# discrim.net
KiCad netlist of a schematic drawn in EAGLE
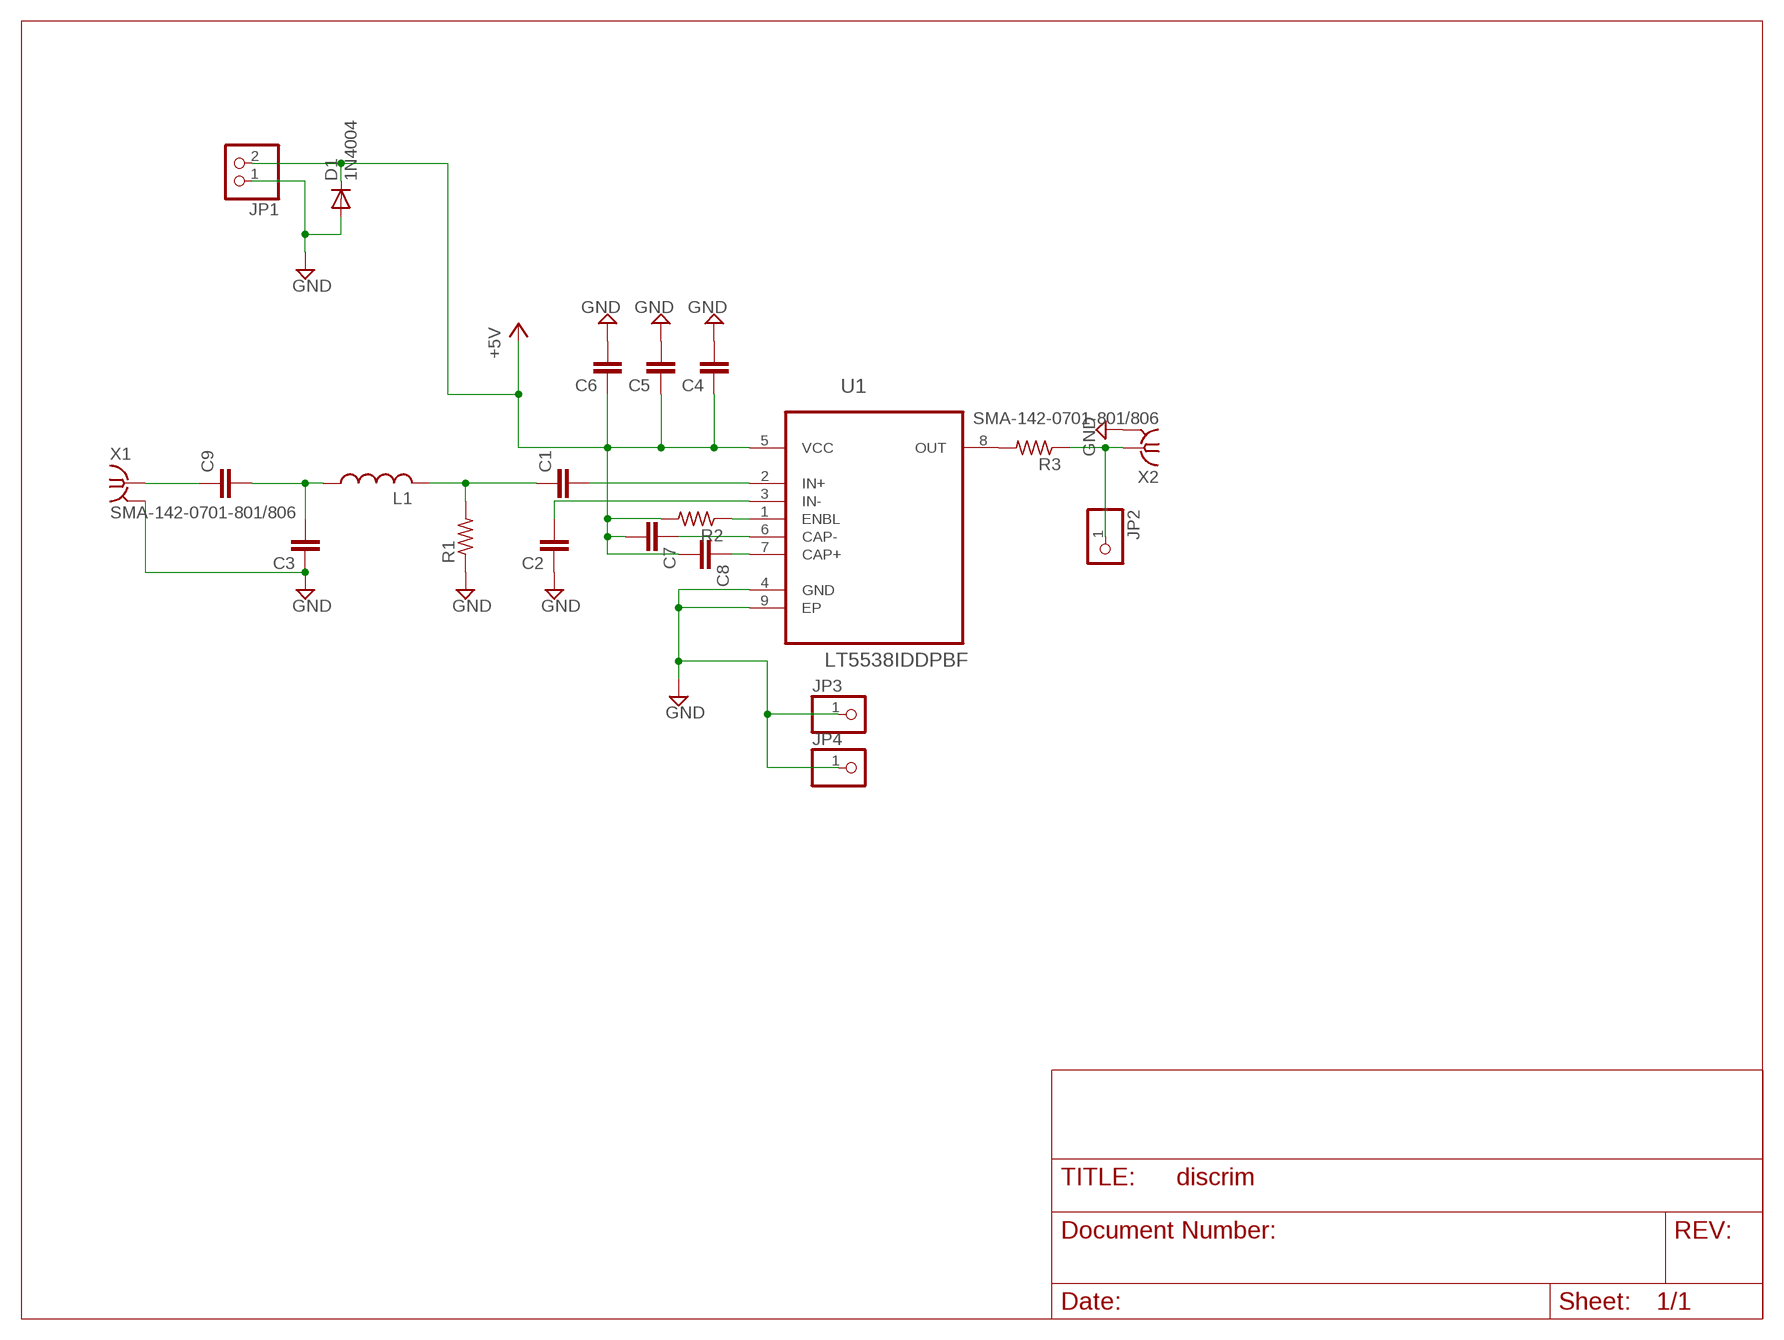
[diagram p0: schematic, sheet 1]

(export (version "E")
  (design (tool "Eeschema 10.0.6"))
  (components
    (comp (ref "C1")
      (value "C-EUC0603")
      (footprint "eagle-import:C0603")
      (libsource (lib "eagle-import") (part "C-EUC0603"))
    )
    (comp (ref "C2")
      (value "C-EUC0603")
      (footprint "eagle-import:C0603")
      (libsource (lib "eagle-import") (part "C-EUC0603"))
    )
    (comp (ref "C3")
      (value "C-EUC0603")
      (footprint "eagle-import:C0603")
      (libsource (lib "eagle-import") (part "C-EUC0603"))
    )
    (comp (ref "C4")
      (value "C-EUC0603")
      (footprint "eagle-import:C0603")
      (libsource (lib "eagle-import") (part "C-EUC0603"))
    )
    (comp (ref "C5")
      (value "C-EUC0603")
      (footprint "eagle-import:C0603")
      (libsource (lib "eagle-import") (part "C-EUC0603"))
    )
    (comp (ref "C6")
      (value "C-EUC0603")
      (footprint "eagle-import:C0603")
      (libsource (lib "eagle-import") (part "C-EUC0603"))
    )
    (comp (ref "C7")
      (value "C-EUC0603")
      (footprint "eagle-import:C0603")
      (libsource (lib "eagle-import") (part "C-EUC0603"))
    )
    (comp (ref "C8")
      (value "C-EUC0603")
      (footprint "eagle-import:C0603")
      (libsource (lib "eagle-import") (part "C-EUC0603"))
    )
    (comp (ref "C9")
      (value "C-EUC0603")
      (footprint "eagle-import:C0603")
      (libsource (lib "eagle-import") (part "C-EUC0603"))
    )
    (comp (ref "D1")
      (value "1N4004")
      (footprint "eagle-import:DO41-10")
      (libsource (lib "eagle-import") (part "1N4004"))
    )
    (comp (ref "JP1")
      (value "PINHD-1X2")
      (footprint "eagle-import:1X02")
      (libsource (lib "eagle-import") (part "PINHD-1X2"))
    )
    (comp (ref "JP2")
      (value "PINHD-1X1")
      (footprint "eagle-import:1X01")
      (libsource (lib "eagle-import") (part "PINHD-1X1"))
    )
    (comp (ref "JP3")
      (value "PINHD-1X1")
      (footprint "eagle-import:1X01")
      (libsource (lib "eagle-import") (part "PINHD-1X1"))
    )
    (comp (ref "JP4")
      (value "PINHD-1X1")
      (footprint "eagle-import:1X01")
      (libsource (lib "eagle-import") (part "PINHD-1X1"))
    )
    (comp (ref "L1")
      (value "L-USL2012C")
      (footprint "eagle-import:L2012C")
      (libsource (lib "eagle-import") (part "L-USL2012C"))
    )
    (comp (ref "R1")
      (value "R-US_R0603")
      (footprint "eagle-import:R0603")
      (libsource (lib "eagle-import") (part "R-US_R0603"))
    )
    (comp (ref "R2")
      (value "R-US_R0603")
      (footprint "eagle-import:R0603")
      (libsource (lib "eagle-import") (part "R-US_R0603"))
    )
    (comp (ref "R3")
      (value "R-US_R0603")
      (footprint "eagle-import:R0603")
      (libsource (lib "eagle-import") (part "R-US_R0603"))
    )
    (comp (ref "U1")
      (value "LT5538IDDPBF")
      (footprint "eagle-import:DFN300X300X80-9N")
      (fields (field (name "MPN") "LT5538IDD#PBF"))
      (libsource (lib "eagle-import") (part "LT5538IDDPBF"))
    )
    (comp (ref "X1")
      (value "SMA-142-0701-801/806")
      (footprint "eagle-import:J502-ND-142-0701-801_806")
      (fields (field (name "MF") "JOHNSON COMPONENTS") (field (name "MPN") "142-0701-801"))
      (libsource (lib "eagle-import") (part "SMA-142-0701-801/806"))
    )
    (comp (ref "X2")
      (value "SMA-142-0701-801/806")
      (footprint "eagle-import:J502-ND-142-0701-801_806")
      (fields (field (name "MF") "JOHNSON COMPONENTS") (field (name "MPN") "142-0701-801"))
      (libsource (lib "eagle-import") (part "SMA-142-0701-801/806"))
    )
  )
  (nets
    (net (code "1") (name "+5V") (class "Default")
      (node (ref "C4") (pin "1") (pinfunction "1_1") (pintype "passive"))
      (node (ref "C5") (pin "1") (pinfunction "1_1") (pintype "passive"))
      (node (ref "C6") (pin "1") (pinfunction "1_1") (pintype "passive"))
      (node (ref "C7") (pin "2") (pinfunction "2_2") (pintype "passive"))
      (node (ref "C8") (pin "2") (pinfunction "2_2") (pintype "passive"))
      (node (ref "D1") (pin "C") (pinfunction "C_C") (pintype "passive"))
      (node (ref "JP1") (pin "2") (pinfunction "2_2") (pintype "passive"))
      (node (ref "R2") (pin "2") (pinfunction "2_2") (pintype "passive"))
      (node (ref "U1") (pin "5") (pinfunction "VCC_5") (pintype "power_in"))
    )
    (net (code "2") (name "GND") (class "Default")
      (node (ref "C2") (pin "1") (pinfunction "1_1") (pintype "passive"))
      (node (ref "C3") (pin "1") (pinfunction "1_1") (pintype "passive"))
      (node (ref "C4") (pin "2") (pinfunction "2_2") (pintype "passive"))
      (node (ref "C5") (pin "2") (pinfunction "2_2") (pintype "passive"))
      (node (ref "C6") (pin "2") (pinfunction "2_2") (pintype "passive"))
      (node (ref "D1") (pin "A") (pinfunction "A_A") (pintype "passive"))
      (node (ref "JP1") (pin "1") (pinfunction "1_1") (pintype "passive"))
      (node (ref "JP3") (pin "1") (pinfunction "1_1") (pintype "passive"))
      (node (ref "JP4") (pin "1") (pinfunction "1_1") (pintype "passive"))
      (node (ref "R1") (pin "1") (pinfunction "1_1") (pintype "passive"))
      (node (ref "U1") (pin "4") (pinfunction "GND_4") (pintype "passive"))
      (node (ref "U1") (pin "9") (pinfunction "EP_9") (pintype "passive"))
      (node (ref "X1") (pin "G@1") (pinfunction "2_G@1") (pintype "passive"))
      (node (ref "X1") (pin "G@2") (pinfunction "2_G@2") (pintype "passive"))
      (node (ref "X1") (pin "G@3") (pinfunction "2_G@3") (pintype "passive"))
      (node (ref "X1") (pin "G@4") (pinfunction "2_G@4") (pintype "passive"))
      (node (ref "X2") (pin "G@1") (pinfunction "2_G@1") (pintype "passive"))
      (node (ref "X2") (pin "G@2") (pinfunction "2_G@2") (pintype "passive"))
      (node (ref "X2") (pin "G@3") (pinfunction "2_G@3") (pintype "passive"))
      (node (ref "X2") (pin "G@4") (pinfunction "2_G@4") (pintype "passive"))
    )
    (net (code "3") (name "Net-(C1-Pad1)") (class "Default")
      (node (ref "C1") (pin "1") (pinfunction "1_1") (pintype "passive"))
      (node (ref "L1") (pin "2") (pinfunction "2_2") (pintype "passive"))
      (node (ref "R1") (pin "2") (pinfunction "2_2") (pintype "passive"))
    )
    (net (code "4") (name "Net-(C3-Pad2)") (class "Default")
      (node (ref "C3") (pin "2") (pinfunction "2_2") (pintype "passive"))
      (node (ref "C9") (pin "2") (pinfunction "2_2") (pintype "passive"))
      (node (ref "L1") (pin "1") (pinfunction "1_1") (pintype "passive"))
    )
    (net (code "5") (name "Net-(C9-Pad1)") (class "Default")
      (node (ref "C9") (pin "1") (pinfunction "1_1") (pintype "passive"))
      (node (ref "X1") (pin "1") (pinfunction "1_1") (pintype "passive"))
    )
    (net (code "6") (name "Net-(JP2-Pad1)") (class "Default")
      (node (ref "JP2") (pin "1") (pinfunction "1_1") (pintype "passive"))
      (node (ref "R3") (pin "1") (pinfunction "1_1") (pintype "passive"))
      (node (ref "X2") (pin "1") (pinfunction "1_1") (pintype "passive"))
    )
    (net (code "7") (name "Net-(U1-CAP+)") (class "Default")
      (node (ref "C8") (pin "1") (pinfunction "1_1") (pintype "passive"))
      (node (ref "U1") (pin "7") (pinfunction "CAP+_7") (pintype "passive"))
    )
    (net (code "8") (name "Net-(U1-CAP-)") (class "Default")
      (node (ref "C7") (pin "1") (pinfunction "1_1") (pintype "passive"))
      (node (ref "U1") (pin "6") (pinfunction "CAP-_6") (pintype "passive"))
    )
    (net (code "9") (name "Net-(U1-ENBL)") (class "Default")
      (node (ref "R2") (pin "1") (pinfunction "1_1") (pintype "passive"))
      (node (ref "U1") (pin "1") (pinfunction "ENBL_1") (pintype "input"))
    )
    (net (code "10") (name "Net-(U1-IN+)") (class "Default")
      (node (ref "C1") (pin "2") (pinfunction "2_2") (pintype "passive"))
      (node (ref "U1") (pin "2") (pinfunction "IN+_2") (pintype "input"))
    )
    (net (code "11") (name "Net-(U1-IN-)") (class "Default")
      (node (ref "C2") (pin "2") (pinfunction "2_2") (pintype "passive"))
      (node (ref "U1") (pin "3") (pinfunction "IN-_3") (pintype "input"))
    )
    (net (code "12") (name "Net-(U1-OUT)") (class "Default")
      (node (ref "R3") (pin "2") (pinfunction "2_2") (pintype "passive"))
      (node (ref "U1") (pin "8") (pinfunction "OUT_8") (pintype "output"))
    )
  )
)
